# MM_BeanServoShield_v1_2.net
KiCad netlist of a schematic drawn in EAGLE
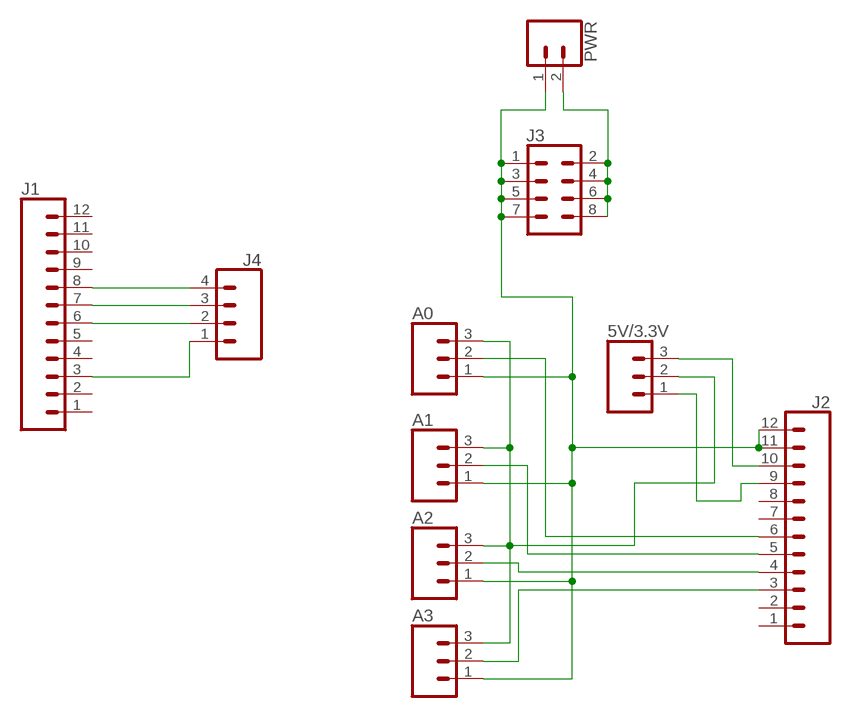
[diagram p0: schematic, sheet 1]

(export (version "E")
  (design (tool "Eeschema 10.0.6"))
  (components
    (comp (ref "5V/3.3V")
      (value "CONN_03")
      (footprint "eagle-import:1X03")
      (libsource (lib "eagle-import") (part "CONN_03"))
    )
    (comp (ref "A0")
      (value "CONN_03POLAR")
      (footprint "eagle-import:MOLEX-1X3")
      (libsource (lib "eagle-import") (part "CONN_03POLAR"))
    )
    (comp (ref "A1")
      (value "CONN_03POLAR")
      (footprint "eagle-import:MOLEX-1X3")
      (libsource (lib "eagle-import") (part "CONN_03POLAR"))
    )
    (comp (ref "A2")
      (value "CONN_03POLAR")
      (footprint "eagle-import:MOLEX-1X3")
      (libsource (lib "eagle-import") (part "CONN_03POLAR"))
    )
    (comp (ref "A3")
      (value "CONN_03POLAR")
      (footprint "eagle-import:MOLEX-1X3")
      (libsource (lib "eagle-import") (part "CONN_03POLAR"))
    )
    (comp (ref "J1")
      (value "CONN_12")
      (footprint "eagle-import:1X12")
      (libsource (lib "eagle-import") (part "CONN_12"))
    )
    (comp (ref "J2")
      (value "CONN_12")
      (footprint "eagle-import:1X12")
      (libsource (lib "eagle-import") (part "CONN_12"))
    )
    (comp (ref "J3")
      (value "CONN_04X2")
      (footprint "eagle-import:2X4")
      (libsource (lib "eagle-import") (part "CONN_04X2"))
    )
    (comp (ref "J4")
      (value "CONN_04")
      (footprint "eagle-import:1X04")
      (libsource (lib "eagle-import") (part "CONN_04"))
    )
    (comp (ref "PWR")
      (value "CONN_02POLAR")
      (footprint "eagle-import:MOLEX-1X2")
      (libsource (lib "eagle-import") (part "CONN_02POLAR"))
    )
  )
  (nets
    (net (code "1") (name "Net-(5V/3.3V-Pad1)") (class "Default")
      (node (ref "5V/3.3V") (pin "1") (pinfunction "1_1") (pintype "passive"))
      (node (ref "J2") (pin "9") (pinfunction "9_9") (pintype "passive"))
    )
    (net (code "2") (name "Net-(5V/3.3V-Pad2)") (class "Default")
      (node (ref "5V/3.3V") (pin "2") (pinfunction "2_2") (pintype "passive"))
      (node (ref "A0") (pin "3") (pinfunction "3_3") (pintype "passive"))
      (node (ref "A1") (pin "3") (pinfunction "3_3") (pintype "passive"))
      (node (ref "A2") (pin "3") (pinfunction "3_3") (pintype "passive"))
      (node (ref "A3") (pin "3") (pinfunction "3_3") (pintype "passive"))
    )
    (net (code "3") (name "Net-(5V/3.3V-Pad3)") (class "Default")
      (node (ref "5V/3.3V") (pin "3") (pinfunction "3_3") (pintype "passive"))
      (node (ref "J2") (pin "10") (pinfunction "10_10") (pintype "passive"))
    )
    (net (code "4") (name "Net-(A0-Pad1)") (class "Default")
      (node (ref "A0") (pin "1") (pinfunction "1_1") (pintype "passive"))
      (node (ref "A1") (pin "1") (pinfunction "1_1") (pintype "passive"))
      (node (ref "A2") (pin "1") (pinfunction "1_1") (pintype "passive"))
      (node (ref "A3") (pin "1") (pinfunction "1_1") (pintype "passive"))
      (node (ref "J2") (pin "11") (pinfunction "11_11") (pintype "passive"))
      (node (ref "J2") (pin "12") (pinfunction "12_12") (pintype "passive"))
      (node (ref "J3") (pin "1") (pinfunction "1_1") (pintype "passive"))
      (node (ref "J3") (pin "3") (pinfunction "3_3") (pintype "passive"))
      (node (ref "J3") (pin "5") (pinfunction "5_5") (pintype "passive"))
      (node (ref "J3") (pin "7") (pinfunction "7_7") (pintype "passive"))
      (node (ref "PWR") (pin "1") (pinfunction "1_1") (pintype "passive"))
    )
    (net (code "5") (name "Net-(A0-Pad2)") (class "Default")
      (node (ref "A0") (pin "2") (pinfunction "2_2") (pintype "passive"))
      (node (ref "J2") (pin "6") (pinfunction "6_6") (pintype "passive"))
    )
    (net (code "6") (name "Net-(A1-Pad2)") (class "Default")
      (node (ref "A1") (pin "2") (pinfunction "2_2") (pintype "passive"))
      (node (ref "J2") (pin "5") (pinfunction "5_5") (pintype "passive"))
    )
    (net (code "7") (name "Net-(A2-Pad2)") (class "Default")
      (node (ref "A2") (pin "2") (pinfunction "2_2") (pintype "passive"))
      (node (ref "J2") (pin "4") (pinfunction "4_4") (pintype "passive"))
    )
    (net (code "8") (name "Net-(A3-Pad2)") (class "Default")
      (node (ref "A3") (pin "2") (pinfunction "2_2") (pintype "passive"))
      (node (ref "J2") (pin "3") (pinfunction "3_3") (pintype "passive"))
    )
    (net (code "9") (name "Net-(J1-Pad3)") (class "Default")
      (node (ref "J1") (pin "3") (pinfunction "3_3") (pintype "passive"))
      (node (ref "J4") (pin "1") (pinfunction "1_1") (pintype "passive"))
    )
    (net (code "10") (name "Net-(J1-Pad6)") (class "Default")
      (node (ref "J1") (pin "6") (pinfunction "6_6") (pintype "passive"))
      (node (ref "J4") (pin "2") (pinfunction "2_2") (pintype "passive"))
    )
    (net (code "11") (name "Net-(J1-Pad7)") (class "Default")
      (node (ref "J1") (pin "7") (pinfunction "7_7") (pintype "passive"))
      (node (ref "J4") (pin "3") (pinfunction "3_3") (pintype "passive"))
    )
    (net (code "12") (name "Net-(J1-Pad8)") (class "Default")
      (node (ref "J1") (pin "8") (pinfunction "8_8") (pintype "passive"))
      (node (ref "J4") (pin "4") (pinfunction "4_4") (pintype "passive"))
    )
    (net (code "13") (name "Net-(J3-Pad2)") (class "Default")
      (node (ref "J3") (pin "2") (pinfunction "2_2") (pintype "passive"))
      (node (ref "J3") (pin "4") (pinfunction "4_4") (pintype "passive"))
      (node (ref "J3") (pin "6") (pinfunction "6_6") (pintype "passive"))
      (node (ref "J3") (pin "8") (pinfunction "8_8") (pintype "passive"))
      (node (ref "PWR") (pin "2") (pinfunction "2_2") (pintype "passive"))
    )
    (net (code "14") (name "unconnected-(J1-Pad1)") (class "Default")
      (node (ref "J1") (pin "1") (pinfunction "1_1") (pintype "passive"))
    )
    (net (code "15") (name "unconnected-(J1-Pad2)") (class "Default")
      (node (ref "J1") (pin "2") (pinfunction "2_2") (pintype "passive"))
    )
    (net (code "16") (name "unconnected-(J1-Pad4)") (class "Default")
      (node (ref "J1") (pin "4") (pinfunction "4_4") (pintype "passive"))
    )
    (net (code "17") (name "unconnected-(J1-Pad5)") (class "Default")
      (node (ref "J1") (pin "5") (pinfunction "5_5") (pintype "passive"))
    )
    (net (code "18") (name "unconnected-(J1-Pad9)") (class "Default")
      (node (ref "J1") (pin "9") (pinfunction "9_9") (pintype "passive"))
    )
    (net (code "19") (name "unconnected-(J1-Pad10)") (class "Default")
      (node (ref "J1") (pin "10") (pinfunction "10_10") (pintype "passive"))
    )
    (net (code "20") (name "unconnected-(J1-Pad11)") (class "Default")
      (node (ref "J1") (pin "11") (pinfunction "11_11") (pintype "passive"))
    )
    (net (code "21") (name "unconnected-(J1-Pad12)") (class "Default")
      (node (ref "J1") (pin "12") (pinfunction "12_12") (pintype "passive"))
    )
    (net (code "22") (name "unconnected-(J2-Pad1)") (class "Default")
      (node (ref "J2") (pin "1") (pinfunction "1_1") (pintype "passive"))
    )
    (net (code "23") (name "unconnected-(J2-Pad2)") (class "Default")
      (node (ref "J2") (pin "2") (pinfunction "2_2") (pintype "passive"))
    )
    (net (code "24") (name "unconnected-(J2-Pad7)") (class "Default")
      (node (ref "J2") (pin "7") (pinfunction "7_7") (pintype "passive"))
    )
    (net (code "25") (name "unconnected-(J2-Pad8)") (class "Default")
      (node (ref "J2") (pin "8") (pinfunction "8_8") (pintype "passive"))
    )
  )
)
